# Adapter-robot.net
KiCad netlist of a schematic drawn in EAGLE
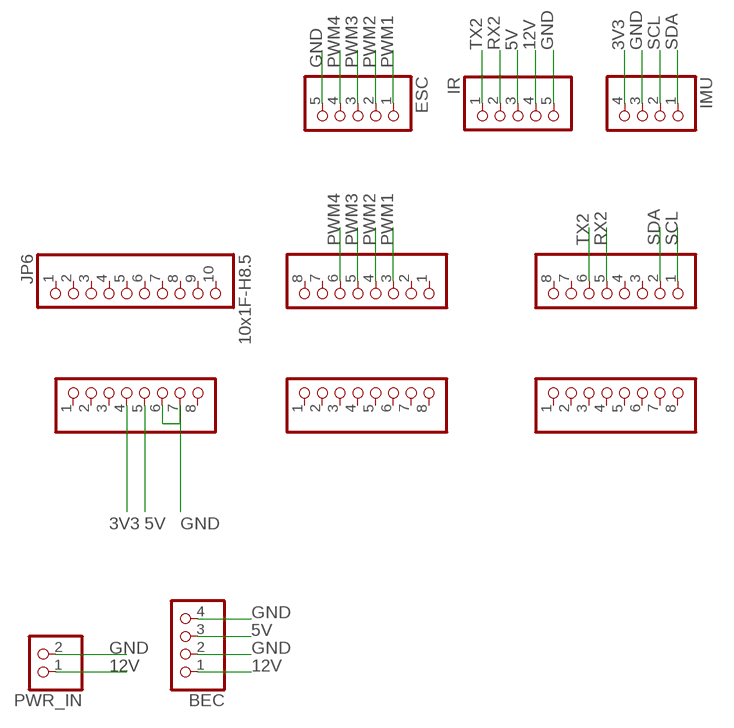
[diagram p0: schematic, sheet 1]

(export (version "E")
  (design (tool "Eeschema 10.0.6"))
  (components
    (comp (ref "ADCH")
      (value "8x1F-H8.5")
      (footprint "eagle-import:1X08")
      (libsource (lib "eagle-import") (part "PINHD-1X8"))
    )
    (comp (ref "ADCL")
      (value "8x1F-H8.5")
      (footprint "eagle-import:1X08")
      (libsource (lib "eagle-import") (part "PINHD-1X8"))
    )
    (comp (ref "BEC")
      (value "PINHD-1X4")
      (footprint "eagle-import:1X04")
      (libsource (lib "eagle-import") (part "PINHD-1X4"))
    )
    (comp (ref "COMMUNICATION")
      (value "8x1F-H8.5")
      (footprint "eagle-import:1X08")
      (libsource (lib "eagle-import") (part "PINHD-1X8"))
    )
    (comp (ref "ESC")
      (value "PINHD-1X5")
      (footprint "eagle-import:1X05")
      (libsource (lib "eagle-import") (part "PINHD-1X5"))
    )
    (comp (ref "IMU")
      (value "PINHD-1X4")
      (footprint "eagle-import:1X04")
      (libsource (lib "eagle-import") (part "PINHD-1X4"))
    )
    (comp (ref "IR")
      (value "PINHD-1X5")
      (footprint "eagle-import:1X05")
      (libsource (lib "eagle-import") (part "PINHD-1X5"))
    )
    (comp (ref "JP6")
      (value "10x1F-H8.5")
      (footprint "eagle-import:1X10")
      (libsource (lib "eagle-import") (part "PINHD-1X10_ARD"))
    )
    (comp (ref "POWER")
      (value "8x1F-H8.5")
      (footprint "eagle-import:1X08")
      (libsource (lib "eagle-import") (part "PINHD-1X8"))
    )
    (comp (ref "PWML")
      (value "8x1F-H8.5")
      (footprint "eagle-import:1X08")
      (libsource (lib "eagle-import") (part "PINHD-1X8"))
    )
    (comp (ref "PWR_IN")
      (value "PINHD-1X2")
      (footprint "eagle-import:1X02")
      (libsource (lib "eagle-import") (part "PINHD-1X2"))
    )
  )
  (nets
    (net (code "1") (name "/3V3") (class "Default")
      (node (ref "IMU") (pin "4") (pinfunction "4_4") (pintype "passive"))
      (node (ref "POWER") (pin "4") (pinfunction "4_4") (pintype "passive"))
    )
    (net (code "2") (name "/5V") (class "Default")
      (node (ref "BEC") (pin "3") (pinfunction "3_3") (pintype "passive"))
      (node (ref "IR") (pin "3") (pinfunction "3_3") (pintype "passive"))
      (node (ref "POWER") (pin "5") (pinfunction "5_5") (pintype "passive"))
    )
    (net (code "3") (name "/12V") (class "Default")
      (node (ref "BEC") (pin "1") (pinfunction "1_1") (pintype "passive"))
      (node (ref "IR") (pin "4") (pinfunction "4_4") (pintype "passive"))
      (node (ref "PWR_IN") (pin "1") (pinfunction "1_1") (pintype "passive"))
    )
    (net (code "4") (name "/GND") (class "Default")
      (node (ref "BEC") (pin "2") (pinfunction "2_2") (pintype "passive"))
      (node (ref "BEC") (pin "4") (pinfunction "4_4") (pintype "passive"))
      (node (ref "ESC") (pin "5") (pinfunction "5_5") (pintype "passive"))
      (node (ref "IMU") (pin "3") (pinfunction "3_3") (pintype "passive"))
      (node (ref "IR") (pin "5") (pinfunction "5_5") (pintype "passive"))
      (node (ref "POWER") (pin "6") (pinfunction "6_6") (pintype "passive"))
      (node (ref "POWER") (pin "7") (pinfunction "7_7") (pintype "passive"))
      (node (ref "PWR_IN") (pin "2") (pinfunction "2_2") (pintype "passive"))
    )
    (net (code "5") (name "/PWM1") (class "Default")
      (node (ref "ESC") (pin "1") (pinfunction "1_1") (pintype "passive"))
      (node (ref "PWML") (pin "3") (pinfunction "3_3") (pintype "passive"))
    )
    (net (code "6") (name "/PWM2") (class "Default")
      (node (ref "ESC") (pin "2") (pinfunction "2_2") (pintype "passive"))
      (node (ref "PWML") (pin "4") (pinfunction "4_4") (pintype "passive"))
    )
    (net (code "7") (name "/PWM3") (class "Default")
      (node (ref "ESC") (pin "3") (pinfunction "3_3") (pintype "passive"))
      (node (ref "PWML") (pin "5") (pinfunction "5_5") (pintype "passive"))
    )
    (net (code "8") (name "/PWM4") (class "Default")
      (node (ref "ESC") (pin "4") (pinfunction "4_4") (pintype "passive"))
      (node (ref "PWML") (pin "6") (pinfunction "6_6") (pintype "passive"))
    )
    (net (code "9") (name "/RX2") (class "Default")
      (node (ref "COMMUNICATION") (pin "5") (pinfunction "5_5") (pintype "passive"))
      (node (ref "IR") (pin "2") (pinfunction "2_2") (pintype "passive"))
    )
    (net (code "10") (name "/SCL") (class "Default")
      (node (ref "COMMUNICATION") (pin "1") (pinfunction "1_1") (pintype "passive"))
      (node (ref "IMU") (pin "2") (pinfunction "2_2") (pintype "passive"))
    )
    (net (code "11") (name "/SDA") (class "Default")
      (node (ref "COMMUNICATION") (pin "2") (pinfunction "2_2") (pintype "passive"))
      (node (ref "IMU") (pin "1") (pinfunction "1_1") (pintype "passive"))
    )
    (net (code "12") (name "/TX2") (class "Default")
      (node (ref "COMMUNICATION") (pin "6") (pinfunction "6_6") (pintype "passive"))
      (node (ref "IR") (pin "1") (pinfunction "1_1") (pintype "passive"))
    )
    (net (code "13") (name "unconnected-(ADCH-Pad1)") (class "Default")
      (node (ref "ADCH") (pin "1") (pinfunction "1_1") (pintype "passive"))
    )
    (net (code "14") (name "unconnected-(ADCH-Pad2)") (class "Default")
      (node (ref "ADCH") (pin "2") (pinfunction "2_2") (pintype "passive"))
    )
    (net (code "15") (name "unconnected-(ADCH-Pad3)") (class "Default")
      (node (ref "ADCH") (pin "3") (pinfunction "3_3") (pintype "passive"))
    )
    (net (code "16") (name "unconnected-(ADCH-Pad4)") (class "Default")
      (node (ref "ADCH") (pin "4") (pinfunction "4_4") (pintype "passive"))
    )
    (net (code "17") (name "unconnected-(ADCH-Pad5)") (class "Default")
      (node (ref "ADCH") (pin "5") (pinfunction "5_5") (pintype "passive"))
    )
    (net (code "18") (name "unconnected-(ADCH-Pad6)") (class "Default")
      (node (ref "ADCH") (pin "6") (pinfunction "6_6") (pintype "passive"))
    )
    (net (code "19") (name "unconnected-(ADCH-Pad7)") (class "Default")
      (node (ref "ADCH") (pin "7") (pinfunction "7_7") (pintype "passive"))
    )
    (net (code "20") (name "unconnected-(ADCH-Pad8)") (class "Default")
      (node (ref "ADCH") (pin "8") (pinfunction "8_8") (pintype "passive"))
    )
    (net (code "21") (name "unconnected-(ADCL-Pad1)") (class "Default")
      (node (ref "ADCL") (pin "1") (pinfunction "1_1") (pintype "passive"))
    )
    (net (code "22") (name "unconnected-(ADCL-Pad2)") (class "Default")
      (node (ref "ADCL") (pin "2") (pinfunction "2_2") (pintype "passive"))
    )
    (net (code "23") (name "unconnected-(ADCL-Pad3)") (class "Default")
      (node (ref "ADCL") (pin "3") (pinfunction "3_3") (pintype "passive"))
    )
    (net (code "24") (name "unconnected-(ADCL-Pad4)") (class "Default")
      (node (ref "ADCL") (pin "4") (pinfunction "4_4") (pintype "passive"))
    )
    (net (code "25") (name "unconnected-(ADCL-Pad5)") (class "Default")
      (node (ref "ADCL") (pin "5") (pinfunction "5_5") (pintype "passive"))
    )
    (net (code "26") (name "unconnected-(ADCL-Pad6)") (class "Default")
      (node (ref "ADCL") (pin "6") (pinfunction "6_6") (pintype "passive"))
    )
    (net (code "27") (name "unconnected-(ADCL-Pad7)") (class "Default")
      (node (ref "ADCL") (pin "7") (pinfunction "7_7") (pintype "passive"))
    )
    (net (code "28") (name "unconnected-(ADCL-Pad8)") (class "Default")
      (node (ref "ADCL") (pin "8") (pinfunction "8_8") (pintype "passive"))
    )
    (net (code "29") (name "unconnected-(COMMUNICATION-Pad3)") (class "Default")
      (node (ref "COMMUNICATION") (pin "3") (pinfunction "3_3") (pintype "passive"))
    )
    (net (code "30") (name "unconnected-(COMMUNICATION-Pad4)") (class "Default")
      (node (ref "COMMUNICATION") (pin "4") (pinfunction "4_4") (pintype "passive"))
    )
    (net (code "31") (name "unconnected-(COMMUNICATION-Pad7)") (class "Default")
      (node (ref "COMMUNICATION") (pin "7") (pinfunction "7_7") (pintype "passive"))
    )
    (net (code "32") (name "unconnected-(COMMUNICATION-Pad8)") (class "Default")
      (node (ref "COMMUNICATION") (pin "8") (pinfunction "8_8") (pintype "passive"))
    )
    (net (code "33") (name "unconnected-(JP6-Pad1)") (class "Default")
      (node (ref "JP6") (pin "1") (pinfunction "1_1") (pintype "passive"))
    )
    (net (code "34") (name "unconnected-(JP6-Pad2)") (class "Default")
      (node (ref "JP6") (pin "2") (pinfunction "2_2") (pintype "passive"))
    )
    (net (code "35") (name "unconnected-(JP6-Pad3)") (class "Default")
      (node (ref "JP6") (pin "3") (pinfunction "3_3") (pintype "passive"))
    )
    (net (code "36") (name "unconnected-(JP6-Pad4)") (class "Default")
      (node (ref "JP6") (pin "4") (pinfunction "4_4") (pintype "passive"))
    )
    (net (code "37") (name "unconnected-(JP6-Pad5)") (class "Default")
      (node (ref "JP6") (pin "5") (pinfunction "5_5") (pintype "passive"))
    )
    (net (code "38") (name "unconnected-(JP6-Pad6)") (class "Default")
      (node (ref "JP6") (pin "6") (pinfunction "6_6") (pintype "passive"))
    )
    (net (code "39") (name "unconnected-(JP6-Pad7)") (class "Default")
      (node (ref "JP6") (pin "7") (pinfunction "7_7") (pintype "passive"))
    )
    (net (code "40") (name "unconnected-(JP6-Pad8)") (class "Default")
      (node (ref "JP6") (pin "8") (pinfunction "8_8") (pintype "passive"))
    )
    (net (code "41") (name "unconnected-(JP6-Pad9)") (class "Default")
      (node (ref "JP6") (pin "9") (pinfunction "9_9") (pintype "passive"))
    )
    (net (code "42") (name "unconnected-(JP6-Pad10)") (class "Default")
      (node (ref "JP6") (pin "10") (pinfunction "10_10") (pintype "passive"))
    )
    (net (code "43") (name "unconnected-(POWER-Pad1)") (class "Default")
      (node (ref "POWER") (pin "1") (pinfunction "1_1") (pintype "passive"))
    )
    (net (code "44") (name "unconnected-(POWER-Pad2)") (class "Default")
      (node (ref "POWER") (pin "2") (pinfunction "2_2") (pintype "passive"))
    )
    (net (code "45") (name "unconnected-(POWER-Pad3)") (class "Default")
      (node (ref "POWER") (pin "3") (pinfunction "3_3") (pintype "passive"))
    )
    (net (code "46") (name "unconnected-(POWER-Pad8)") (class "Default")
      (node (ref "POWER") (pin "8") (pinfunction "8_8") (pintype "passive"))
    )
    (net (code "47") (name "unconnected-(PWML-Pad1)") (class "Default")
      (node (ref "PWML") (pin "1") (pinfunction "1_1") (pintype "passive"))
    )
    (net (code "48") (name "unconnected-(PWML-Pad2)") (class "Default")
      (node (ref "PWML") (pin "2") (pinfunction "2_2") (pintype "passive"))
    )
    (net (code "49") (name "unconnected-(PWML-Pad7)") (class "Default")
      (node (ref "PWML") (pin "7") (pinfunction "7_7") (pintype "passive"))
    )
    (net (code "50") (name "unconnected-(PWML-Pad8)") (class "Default")
      (node (ref "PWML") (pin "8") (pinfunction "8_8") (pintype "passive"))
    )
  )
)
